# STO.net
KiCad netlist of a schematic drawn in Altium Designer
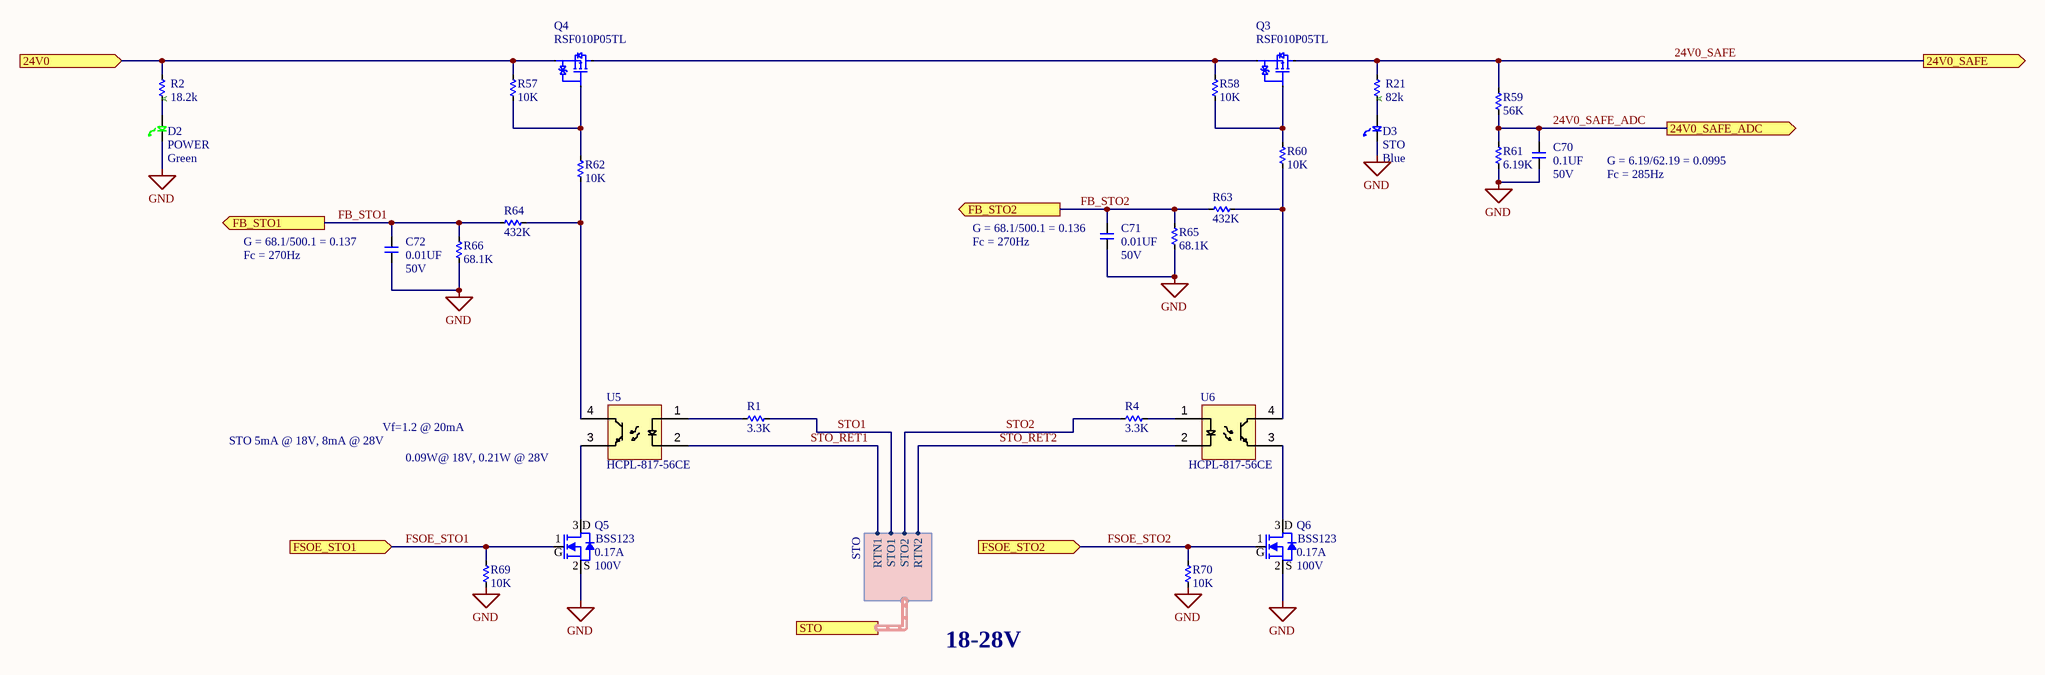
[diagram p0: STO.SchDoc]

(export (version "E")
  (design (tool "Eeschema 10.0.6"))
  (components
    (comp (ref "C70")
      (value "0.1UF")
      (footprint "C0402")
      (description "CAP, CER, X5R, 0.1uF, 10%, 50V, 0402, 0.55mm")
      (fields (field (name "MFG") "YAGEO") (field (name "VOLTAGE") "50V") (field (name "TOLERANCE") "10%"))
      (libsource (lib "AltiumReleaseLibDB") (part "__Template_Cap"))
    )
    (comp (ref "C71")
      (value "0.01UF")
      (footprint "C0402")
      (description "CAP, CER, X7R, 0.01uF, 50V, 20%, 0402, 0.56mm T")
      (fields (field (name "MFG") "KEMET") (field (name "VOLTAGE") "50V") (field (name "TOLERANCE") "20%"))
      (libsource (lib "AltiumReleaseLibDB") (part "__Template_Cap"))
    )
    (comp (ref "C72")
      (value "0.01UF")
      (footprint "C0402")
      (description "CAP, CER, X7R, 0.01uF, 50V, 20%, 0402, 0.56mm T")
      (fields (field (name "MFG") "KEMET") (field (name "VOLTAGE") "50V") (field (name "TOLERANCE") "20%"))
      (libsource (lib "AltiumReleaseLibDB") (part "__Template_Cap"))
    )
    (comp (ref "D2")
      (value "POWER")
      (footprint "LEDSC160X80X90L40-GREEN")
      (description "LED, GREEN, 569nm, 30mA, CLEAR, 0603")
      (fields
        (field (name "MANUFACTURER") "Lite-On Optoelectronics")
        (field (name "MANUFACTURER PART NUMBER") "LTST-C190GKT")
        (field (name "ALTIUM_VALUE") "Green")
      )
      (libsource (lib "Components") (part "LED-GREEN"))
    )
    (comp (ref "D3")
      (value "STO")
      (footprint "LEDSC160X80X90L40-BLUE")
      (description "LED, BLUE, 470nm, 15mA, DIFFUSED, 0603")
      (fields
        (field (name "MANUFACTURER") "Osram Opto")
        (field (name "MANUFACTURER PART NUMBER") "LB Q39G-L2N2-35-1")
        (field (name "ALTIUM_VALUE") "Blue")
      )
      (libsource (lib "Components") (part "LED-BLUE"))
    )
    (comp (ref "Q3")
      (value "PFET_RSF010P05TL")
      (footprint "TUMT3")
      (description "MOSFET, PWR, P-CH, 45VDS, 1A ID, 460mOhm@ 1A, SMD-3")
      (fields (field (name "MFG") "Rohm Semiconductor") (field (name "MFG P/N") "RSF010P05TL"))
      (libsource (lib "AltiumReleaseLibDB") (part "PFET_RSF010P05TL"))
    )
    (comp (ref "Q4")
      (value "PFET_RSF010P05TL")
      (footprint "TUMT3")
      (description "MOSFET, PWR, P-CH, 45VDS, 1A ID, 460mOhm@ 1A, SMD-3")
      (fields (field (name "MFG") "Rohm Semiconductor") (field (name "MFG P/N") "RSF010P05TL"))
      (libsource (lib "AltiumReleaseLibDB") (part "PFET_RSF010P05TL"))
    )
    (comp (ref "Q5")
      (value "ONSEMI BSS123")
      (footprint "SOT23-3P95_240X110L43N")
      (description "XSTR, MOSFET, ENHANCEMENT MODE, N-CH, 100V, 0.17A, SOT23-3")
      (fields
        (field (name "MANUFACTURER") "ON Semiconductor")
        (field (name "MANUFACTURER PART NUMBER") "BSS123")
        (field (name "PART NUMBER") "480-00042-00")
        (field (name "CURRENT RATING") "0.17A")
        (field (name "VOLTAGE RATING") "100V")
      )
      (libsource (lib "Components") (part "NFET-GSD"))
    )
    (comp (ref "Q6")
      (value "ONSEMI BSS123")
      (footprint "SOT23-3P95_240X110L43N")
      (description "XSTR, MOSFET, ENHANCEMENT MODE, N-CH, 100V, 0.17A, SOT23-3")
      (fields
        (field (name "MANUFACTURER") "ON Semiconductor")
        (field (name "MANUFACTURER PART NUMBER") "BSS123")
        (field (name "PART NUMBER") "480-00042-00")
        (field (name "CURRENT RATING") "0.17A")
        (field (name "VOLTAGE RATING") "100V")
      )
      (libsource (lib "Components") (part "NFET-GSD"))
    )
    (comp (ref "R1")
      (value "3.3K")
      (footprint "R1206")
      (description "Resistor, 3.30K Ohms, 1206, 0.25W, ±1%")
      (fields (field (name "MFG") "STACKPOLE ELECTRONICS") (field (name "POWER") "1/4W"))
      (libsource (lib "AltiumReleaseLibDB") (part "__Template_Resistor"))
    )
    (comp (ref "R2")
      (value "18.2k")
      (footprint "RESC100X50X40L25")
      (description "Res, 18.2k, +/-1%, 0.1W, 0402, AUTO GRADE")
      (fields
        (field (name "MANUFACTURER") "Panasonic")
        (field (name "MANUFACTURER PART NUMBER") "ERJ2RKF1822X")
      )
      (libsource (lib "Components") (part "RES-AUTO"))
    )
    (comp (ref "R4")
      (value "3.3K")
      (footprint "R1206")
      (description "Resistor, 3.30K Ohms, 1206, 0.25W, ±1%")
      (fields (field (name "MFG") "STACKPOLE ELECTRONICS") (field (name "POWER") "1/4W"))
      (libsource (lib "AltiumReleaseLibDB") (part "__Template_Resistor"))
    )
    (comp (ref "R21")
      (value "82k")
      (footprint "RESC100X50X40L25")
      (description "Res, 82k, +/-1%, 0.1W, 0402, AUTO GRADE")
      (fields
        (field (name "MANUFACTURER") "Panasonic")
        (field (name "MANUFACTURER PART NUMBER") "ERJ2RKF8202X")
      )
      (libsource (lib "Components") (part "RES-AUTO"))
    )
    (comp (ref "R57")
      (value "10K")
      (footprint "R0402")
      (description "RES, 10K, 1%, 1/10W, 0402, AUTOGRADE")
      (fields (field (name "MFG") "PANASONIC") (field (name "POWER") "1/10W"))
      (libsource (lib "AltiumReleaseLibDB") (part "__Template_Resistor"))
    )
    (comp (ref "R58")
      (value "10K")
      (footprint "R0402")
      (description "RES, 10K, 1%, 1/10W, 0402, AUTOGRADE")
      (fields (field (name "MFG") "PANASONIC") (field (name "POWER") "1/10W"))
      (libsource (lib "AltiumReleaseLibDB") (part "__Template_Resistor"))
    )
    (comp (ref "R59")
      (value "56K")
      (footprint "R0402")
      (description "RES, 56K, 1%, 1/16W, 0402")
      (fields (field (name "MFG") "VISHAY") (field (name "POWER") "1/16W"))
      (libsource (lib "AltiumReleaseLibDB") (part "__Template_Resistor"))
    )
    (comp (ref "R60")
      (value "10K")
      (footprint "R0402")
      (description "RES, 10K, 1%, 1/10W, 0402, AUTOGRADE")
      (fields (field (name "MFG") "PANASONIC") (field (name "POWER") "1/10W"))
      (libsource (lib "AltiumReleaseLibDB") (part "__Template_Resistor"))
    )
    (comp (ref "R61")
      (value "6.19K")
      (footprint "R0402")
      (description "RES, 6.19K, 1%, 1/16W, 0402")
      (fields (field (name "MFG") "Yageo") (field (name "POWER") "1/16W"))
      (libsource (lib "AltiumReleaseLibDB") (part "__Template_Resistor"))
    )
    (comp (ref "R62")
      (value "10K")
      (footprint "R0402")
      (description "RES, 10K, 1%, 1/10W, 0402, AUTOGRADE")
      (fields (field (name "MFG") "PANASONIC") (field (name "POWER") "1/10W"))
      (libsource (lib "AltiumReleaseLibDB") (part "__Template_Resistor"))
    )
    (comp (ref "R63")
      (value "432K")
      (footprint "R0402")
      (description "RES, 432K, 1%, 1/16W, 0402")
      (fields (field (name "MFG") "VISHAY") (field (name "POWER") "1/16W"))
      (libsource (lib "AltiumReleaseLibDB") (part "__Template_Resistor"))
    )
    (comp (ref "R64")
      (value "432K")
      (footprint "R0402")
      (description "RES, 432K, 1%, 1/16W, 0402")
      (fields (field (name "MFG") "VISHAY") (field (name "POWER") "1/16W"))
      (libsource (lib "AltiumReleaseLibDB") (part "__Template_Resistor"))
    )
    (comp (ref "R65")
      (value "68.1K")
      (footprint "R0402")
      (description "RES, 68.1K, 1%, 1/16W, 0402")
      (fields (field (name "MFG") "VISHAY") (field (name "POWER") "1/16W"))
      (libsource (lib "AltiumReleaseLibDB") (part "__Template_Resistor"))
    )
    (comp (ref "R66")
      (value "68.1K")
      (footprint "R0402")
      (description "RES, 68.1K, 1%, 1/16W, 0402")
      (fields (field (name "MFG") "VISHAY") (field (name "POWER") "1/16W"))
      (libsource (lib "AltiumReleaseLibDB") (part "__Template_Resistor"))
    )
    (comp (ref "R69")
      (value "10K")
      (footprint "R0402")
      (description "RES, 10K, 1%, 1/10W, 0402, AUTOGRADE")
      (fields (field (name "MFG") "PANASONIC") (field (name "POWER") "1/10W"))
      (libsource (lib "AltiumReleaseLibDB") (part "__Template_Resistor"))
    )
    (comp (ref "R70")
      (value "10K")
      (footprint "R0402")
      (description "RES, 10K, 1%, 1/10W, 0402, AUTOGRADE")
      (fields (field (name "MFG") "PANASONIC") (field (name "POWER") "1/10W"))
      (libsource (lib "AltiumReleaseLibDB") (part "__Template_Resistor"))
    )
    (comp (ref "U5")
      (value "OPTO_HCPL-817-56CE")
      (footprint "OPTO_HCPL-817-56CE")
      (description "ISOLATOR, OPTOISOLATOR, PHOTO TRANSISTOR, 70V, 50mA, SMD-4")
      (fields (field (name "MFG") "Broadcom Limited") (field (name "MFG P/N") "HCPL-817-56CE"))
      (libsource (lib "AltiumReleaseLibDB") (part "OPTO_HCPL-817-56CE"))
    )
    (comp (ref "U6")
      (value "OPTO_HCPL-817-56CE")
      (footprint "OPTO_HCPL-817-56CE")
      (description "ISOLATOR, OPTOISOLATOR, PHOTO TRANSISTOR, 70V, 50mA, SMD-4")
      (fields (field (name "MFG") "Broadcom Limited") (field (name "MFG P/N") "HCPL-817-56CE"))
      (libsource (lib "") (part "OPTO_HCPL-817-56CE_1"))
    )
  )
  (nets
    (net (code "2") (name "/24V0") (class "Default")
      (node (ref "Q4") (pin "S") (pinfunction "S_S") (pintype "passive"))
      (node (ref "R2") (pin "2") (pintype "passive"))
      (node (ref "R57") (pin "2") (pintype "passive"))
    )
    (net (code "3") (name "/24V0_SAFE") (class "Default")
      (node (ref "Q3") (pin "D") (pinfunction "D_D") (pintype "passive"))
      (node (ref "R21") (pin "2") (pintype "passive"))
      (node (ref "R59") (pin "2") (pintype "passive"))
    )
    (net (code "4") (name "/24V0_SAFE_ADC") (class "Default")
      (node (ref "C70") (pin "1") (pintype "passive"))
      (node (ref "R59") (pin "1") (pintype "passive"))
      (node (ref "R61") (pin "2") (pintype "passive"))
    )
    (net (code "5") (name "/FB_STO1") (class "Default")
      (node (ref "C72") (pin "1") (pintype "passive"))
      (node (ref "R64") (pin "1") (pintype "passive"))
      (node (ref "R66") (pin "2") (pintype "passive"))
    )
    (net (code "6") (name "/FB_STO2") (class "Default")
      (node (ref "C71") (pin "1") (pintype "passive"))
      (node (ref "R63") (pin "1") (pintype "passive"))
      (node (ref "R65") (pin "2") (pintype "passive"))
    )
    (net (code "7") (name "/FSOE_STO1") (class "Default")
      (node (ref "Q5") (pin "1") (pinfunction "G_1") (pintype "passive"))
      (node (ref "R69") (pin "2") (pintype "passive"))
    )
    (net (code "8") (name "/FSOE_STO2") (class "Default")
      (node (ref "Q6") (pin "1") (pinfunction "G_1") (pintype "passive"))
      (node (ref "R70") (pin "2") (pintype "passive"))
    )
    (net (code "9") (name "/STO1") (class "Default") (node (ref "R1") (pin "2") (pintype "passive")))
    (net (code "10") (name "/STO2") (class "Default") (node (ref "R4") (pin "1") (pintype "passive")))
    (net (code "11") (name "/STO_RET1") (class "Default")
      (node (ref "U5") (pin "2") (pinfunction "Cathode_2") (pintype "passive"))
    )
    (net (code "12") (name "/STO_RET2") (class "Default")
      (node (ref "U6") (pin "2") (pinfunction "Cathode_2") (pintype "passive"))
    )
    (net (code "14") (name "GND") (class "Default")
      (node (ref "C70") (pin "2") (pintype "passive"))
      (node (ref "C71") (pin "2") (pintype "passive"))
      (node (ref "C72") (pin "2") (pintype "passive"))
      (node (ref "D2") (pin "1") (pinfunction "CATHODE_1") (pintype "passive"))
      (node (ref "D3") (pin "1") (pinfunction "CATHODE_1") (pintype "passive"))
      (node (ref "Q5") (pin "2") (pinfunction "S_2") (pintype "passive"))
      (node (ref "Q6") (pin "2") (pinfunction "S_2") (pintype "passive"))
      (node (ref "R61") (pin "1") (pintype "passive"))
      (node (ref "R65") (pin "1") (pintype "passive"))
      (node (ref "R66") (pin "1") (pintype "passive"))
      (node (ref "R69") (pin "1") (pintype "passive"))
      (node (ref "R70") (pin "1") (pintype "passive"))
    )
    (net (code "15") (name "Net-(D2-ANODE)") (class "Default")
      (node (ref "D2") (pin "2") (pinfunction "ANODE_2") (pintype "passive"))
      (node (ref "R2") (pin "1") (pintype "passive"))
    )
    (net (code "16") (name "Net-(D3-ANODE)") (class "Default")
      (node (ref "D3") (pin "2") (pinfunction "ANODE_2") (pintype "passive"))
      (node (ref "R21") (pin "1") (pintype "passive"))
    )
    (net (code "17") (name "Net-(Q3-PadG)") (class "Default")
      (node (ref "Q3") (pin "G") (pinfunction "G_G") (pintype "passive"))
      (node (ref "R58") (pin "1") (pintype "passive"))
      (node (ref "R60") (pin "2") (pintype "passive"))
    )
    (net (code "18") (name "Net-(Q3-PadS)") (class "Default")
      (node (ref "Q3") (pin "S") (pinfunction "S_S") (pintype "passive"))
      (node (ref "Q4") (pin "D") (pinfunction "D_D") (pintype "passive"))
      (node (ref "R58") (pin "2") (pintype "passive"))
    )
    (net (code "19") (name "Net-(Q4-PadG)") (class "Default")
      (node (ref "Q4") (pin "G") (pinfunction "G_G") (pintype "passive"))
      (node (ref "R57") (pin "1") (pintype "passive"))
      (node (ref "R62") (pin "2") (pintype "passive"))
    )
    (net (code "20") (name "Net-(Q5-D)") (class "Default")
      (node (ref "Q5") (pin "3") (pinfunction "D_3") (pintype "passive"))
      (node (ref "U5") (pin "3") (pinfunction "Emitter_3") (pintype "passive"))
    )
    (net (code "21") (name "Net-(Q6-D)") (class "Default")
      (node (ref "Q6") (pin "3") (pinfunction "D_3") (pintype "passive"))
      (node (ref "U6") (pin "3") (pinfunction "Emitter_3") (pintype "passive"))
    )
    (net (code "22") (name "Net-(U5-Anode)") (class "Default")
      (node (ref "R1") (pin "1") (pintype "passive"))
      (node (ref "U5") (pin "1") (pinfunction "Anode_1") (pintype "passive"))
    )
    (net (code "23") (name "Net-(U5-Collector)") (class "Default")
      (node (ref "R62") (pin "1") (pintype "passive"))
      (node (ref "R64") (pin "2") (pintype "passive"))
      (node (ref "U5") (pin "4") (pinfunction "Collector_4") (pintype "passive"))
    )
    (net (code "24") (name "Net-(U6-Anode)") (class "Default")
      (node (ref "R4") (pin "2") (pintype "passive"))
      (node (ref "U6") (pin "1") (pinfunction "Anode_1") (pintype "passive"))
    )
    (net (code "25") (name "Net-(U6-Collector)") (class "Default")
      (node (ref "R60") (pin "1") (pintype "passive"))
      (node (ref "R63") (pin "2") (pintype "passive"))
      (node (ref "U6") (pin "4") (pinfunction "Collector_4") (pintype "passive"))
    )
  )
)
